# Acquisition_module.net
KiCad netlist of a schematic drawn in Altium Designer
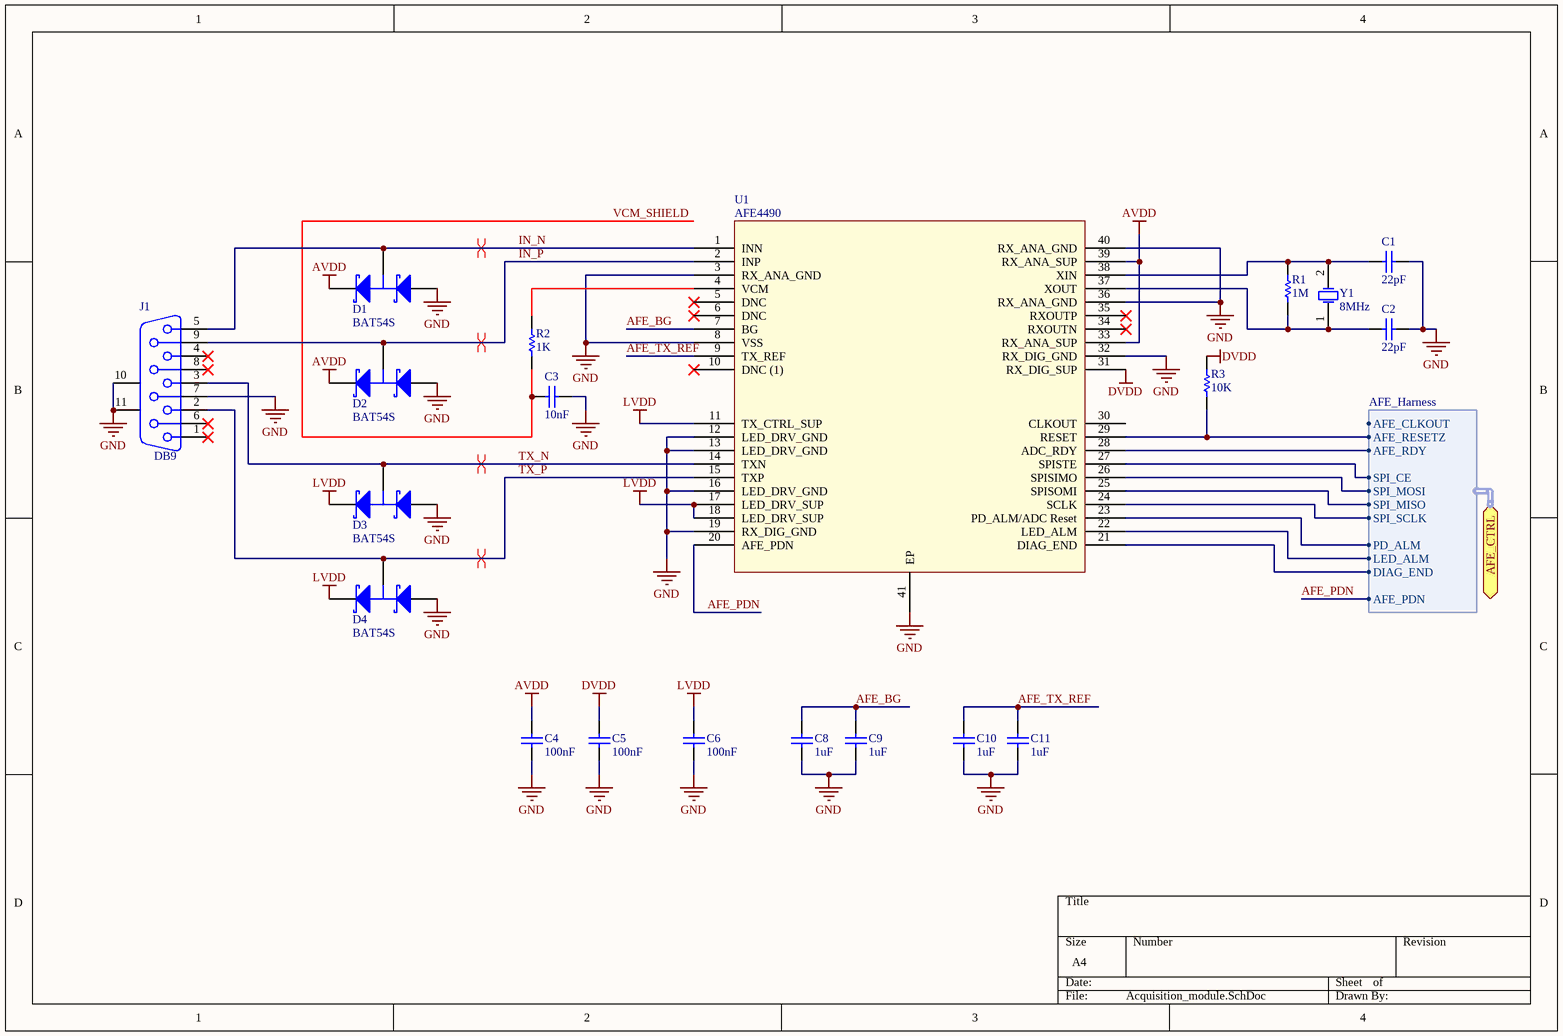
[diagram p0: Acquisition_module.SchDoc]

(export (version "E")
  (design (tool "Eeschema 10.0.6"))
  (components
    (comp (ref "C1")
      (value "22pF")
      (footprint "6-0805_M")
      (description "Capacitor")
      (fields (field (name "Comment") "Cap") (field (name "PUBLISHER") "Altium Limited"))
      (libsource (lib "Miscellaneous Devices") (part "Cap"))
    )
    (comp (ref "C2")
      (value "22pF")
      (footprint "6-0805_M")
      (description "Capacitor")
      (fields (field (name "Comment") "Cap") (field (name "PUBLISHER") "Altium Limited"))
      (libsource (lib "Miscellaneous Devices") (part "Cap"))
    )
    (comp (ref "C3")
      (value "10nF")
      (footprint "6-0805_M")
      (description "Capacitor")
      (fields (field (name "Comment") "Cap") (field (name "PUBLISHER") "Altium Limited"))
      (libsource (lib "Miscellaneous Devices") (part "Cap"))
    )
    (comp (ref "C4")
      (value "100nF")
      (footprint "6-0805_M")
      (description "Capacitor")
      (fields (field (name "Comment") "Cap") (field (name "PUBLISHER") "Altium Limited"))
      (libsource (lib "Miscellaneous Devices") (part "Cap"))
    )
    (comp (ref "C5")
      (value "100nF")
      (footprint "6-0805_M")
      (description "Capacitor")
      (fields (field (name "Comment") "Cap") (field (name "PUBLISHER") "Altium Limited"))
      (libsource (lib "Miscellaneous Devices") (part "Cap"))
    )
    (comp (ref "C6")
      (value "100nF")
      (footprint "6-0805_M")
      (description "Capacitor")
      (fields (field (name "Comment") "Cap") (field (name "PUBLISHER") "Altium Limited"))
      (libsource (lib "Miscellaneous Devices") (part "Cap"))
    )
    (comp (ref "C8")
      (value "1uF")
      (footprint "6-0805_M")
      (description "Capacitor")
      (fields (field (name "Comment") "Cap") (field (name "PUBLISHER") "Altium Limited"))
      (libsource (lib "Miscellaneous Devices") (part "Cap"))
    )
    (comp (ref "C9")
      (value "1uF")
      (footprint "6-0805_M")
      (description "Capacitor")
      (fields (field (name "Comment") "Cap") (field (name "PUBLISHER") "Altium Limited"))
      (libsource (lib "Miscellaneous Devices") (part "Cap"))
    )
    (comp (ref "C10")
      (value "1uF")
      (footprint "6-0805_M")
      (description "Capacitor")
      (fields (field (name "Comment") "Cap") (field (name "PUBLISHER") "Altium Limited"))
      (libsource (lib "Miscellaneous Devices") (part "Cap"))
    )
    (comp (ref "C11")
      (value "1uF")
      (footprint "6-0805_M")
      (description "Capacitor")
      (fields (field (name "Comment") "Cap") (field (name "PUBLISHER") "Altium Limited"))
      (libsource (lib "Miscellaneous Devices") (part "Cap"))
    )
    (comp (ref "D1")
      (value "BAT54S")
      (footprint "SOT23_N")
      (description "Schottky Barrier Double Diode")
      (fields (field (name "PUBLISHER") "Altium Limited"))
      (libsource (lib "Philips Discrete Diode - Schottky") (part "BAT54S"))
    )
    (comp (ref "D2")
      (value "BAT54S")
      (footprint "SOT23_N")
      (description "Schottky Barrier Double Diode")
      (fields (field (name "PUBLISHER") "Altium Limited"))
      (libsource (lib "Philips Discrete Diode - Schottky") (part "BAT54S"))
    )
    (comp (ref "D3")
      (value "BAT54S")
      (footprint "SOT23_N")
      (description "Schottky Barrier Double Diode")
      (fields (field (name "PUBLISHER") "Altium Limited"))
      (libsource (lib "Philips Discrete Diode - Schottky") (part "BAT54S"))
    )
    (comp (ref "D4")
      (value "BAT54S")
      (footprint "SOT23_N")
      (description "Schottky Barrier Double Diode")
      (fields (field (name "PUBLISHER") "Altium Limited"))
      (libsource (lib "Philips Discrete Diode - Schottky") (part "BAT54S"))
    )
    (comp (ref "J1")
      (value "DB9")
      (footprint "DB9")
      (description "Receptacle Assembly, 9 Position, Right Angle")
      (fields (field (name "PUBLISHER") "Altium Limited"))
      (libsource (lib "Miscellaneous Connectors") (part "D Connector 9"))
    )
    (comp (ref "R1")
      (value "1M")
      (footprint "6-0805_M")
      (description "Resistor")
      (fields (field (name "Comment") "Res1") (field (name "PUBLISHER") "Altium Limited"))
      (libsource (lib "Miscellaneous Devices") (part "Res1"))
    )
    (comp (ref "R2")
      (value "1K")
      (footprint "6-0805_M")
      (description "Resistor")
      (fields (field (name "Comment") "Res1") (field (name "PUBLISHER") "Altium Limited"))
      (libsource (lib "Miscellaneous Devices") (part "Res1"))
    )
    (comp (ref "R3")
      (value "10K")
      (footprint "6-0805_M")
      (description "Resistor")
      (fields (field (name "Comment") "Res1") (field (name "PUBLISHER") "Altium Limited"))
      (libsource (lib "Miscellaneous Devices") (part "Res1"))
    )
    (comp (ref "U1")
      (value "AFE4490")
      (footprint "AFE4490QFN50P680X680X100_HS-41N")
      (description "Integrated Analog Front-End for Pulse Oximeters")
      (libsource (lib "AFE4490") (part "AFE4490"))
    )
    (comp (ref "Y1")
      (value "8MHz")
      (footprint "Crystal SMD")
      (description "Crystal Oscillator")
      (fields (field (name "PUBLISHER") "Altium Limited"))
      (libsource (lib "Miscellaneous Devices") (part "XTAL"))
    )
  )
  (nets
    (net (code "2") (name "/AFE_BG") (class "Default")
      (node (ref "C8") (pin "2") (pinfunction "2_2") (pintype "passive"))
      (node (ref "C9") (pin "2") (pinfunction "2_2") (pintype "passive"))
      (node (ref "U1") (pin "7") (pinfunction "BG_7") (pintype "passive"))
    )
    (net (code "3") (name "/AFE_PDN") (class "Default")
      (node (ref "U1") (pin "20") (pinfunction "AFE_PDN_20") (pintype "passive"))
    )
    (net (code "4") (name "/AFE_RDY") (class "Default")
      (node (ref "U1") (pin "28") (pinfunction "ADC_RDY_28") (pintype "passive"))
    )
    (net (code "5") (name "/AFE_RESETZ") (class "Default")
      (node (ref "R3") (pin "1") (pinfunction "1_1") (pintype "passive"))
      (node (ref "U1") (pin "29") (pinfunction "RESET_29") (pintype "passive"))
    )
    (net (code "6") (name "/AFE_TX_REF") (class "Default")
      (node (ref "C10") (pin "2") (pinfunction "2_2") (pintype "passive"))
      (node (ref "C11") (pin "2") (pinfunction "2_2") (pintype "passive"))
      (node (ref "U1") (pin "9") (pinfunction "TX_REF_9") (pintype "passive"))
    )
    (net (code "7") (name "/DIAG_END") (class "Default")
      (node (ref "U1") (pin "21") (pinfunction "DIAG_END_21") (pintype "passive"))
    )
    (net (code "8") (name "/IN_N") (class "Default")
      (node (ref "D1") (pin "3") (pinfunction "C_3") (pintype "passive"))
      (node (ref "J1") (pin "5") (pinfunction "5_5") (pintype "passive"))
      (node (ref "U1") (pin "1") (pinfunction "INN_1") (pintype "passive"))
    )
    (net (code "9") (name "/IN_P") (class "Default")
      (node (ref "D2") (pin "3") (pinfunction "C_3") (pintype "passive"))
      (node (ref "J1") (pin "9") (pinfunction "9_9") (pintype "passive"))
      (node (ref "U1") (pin "2") (pinfunction "INP_2") (pintype "passive"))
    )
    (net (code "10") (name "/LED_ALM") (class "Default")
      (node (ref "U1") (pin "22") (pinfunction "LED_ALM_22") (pintype "passive"))
    )
    (net (code "11") (name "/PD_ALM") (class "Default")
      (node (ref "U1") (pin "23") (pinfunction "PD_ALM/ADC_Reset_23") (pintype "passive"))
    )
    (net (code "12") (name "/SPI_CE") (class "Default")
      (node (ref "U1") (pin "27") (pinfunction "SPISTE_27") (pintype "passive"))
    )
    (net (code "13") (name "/SPI_MISO") (class "Default")
      (node (ref "U1") (pin "25") (pinfunction "SPISOMI_25") (pintype "passive"))
    )
    (net (code "14") (name "/SPI_MOSI") (class "Default")
      (node (ref "U1") (pin "26") (pinfunction "SPISIMO_26") (pintype "passive"))
    )
    (net (code "15") (name "/SPI_SCLK") (class "Default")
      (node (ref "U1") (pin "24") (pinfunction "SCLK_24") (pintype "passive"))
    )
    (net (code "16") (name "/TX_N") (class "Default")
      (node (ref "D3") (pin "3") (pinfunction "C_3") (pintype "passive"))
      (node (ref "J1") (pin "3") (pinfunction "3_3") (pintype "passive"))
      (node (ref "U1") (pin "14") (pinfunction "TXN_14") (pintype "passive"))
    )
    (net (code "17") (name "/TX_P") (class "Default")
      (node (ref "D4") (pin "3") (pinfunction "C_3") (pintype "passive"))
      (node (ref "J1") (pin "2") (pinfunction "2_2") (pintype "passive"))
      (node (ref "U1") (pin "15") (pinfunction "TXP_15") (pintype "passive"))
    )
    (net (code "18") (name "/VCM_SHIELD") (class "Default")
      (node (ref "C3") (pin "2") (pinfunction "2_2") (pintype "passive"))
      (node (ref "R2") (pin "1") (pinfunction "1_1") (pintype "passive"))
    )
    (net (code "20") (name "AVDD") (class "Default")
      (node (ref "C4") (pin "2") (pinfunction "2_2") (pintype "passive"))
      (node (ref "D1") (pin "2") (pinfunction "K_2") (pintype "passive"))
      (node (ref "D2") (pin "2") (pinfunction "K_2") (pintype "passive"))
      (node (ref "U1") (pin "33") (pinfunction "RX_ANA_SUP_33") (pintype "passive"))
      (node (ref "U1") (pin "39") (pinfunction "RX_ANA_SUP_39") (pintype "passive"))
    )
    (net (code "21") (name "DVDD") (class "Default")
      (node (ref "C5") (pin "2") (pinfunction "2_2") (pintype "passive"))
      (node (ref "R3") (pin "2") (pinfunction "2_2") (pintype "passive"))
      (node (ref "U1") (pin "31") (pinfunction "RX_DIG_SUP_31") (pintype "passive"))
    )
    (net (code "22") (name "GND") (class "Default")
      (node (ref "C1") (pin "1") (pinfunction "1_1") (pintype "passive"))
      (node (ref "C10") (pin "1") (pinfunction "1_1") (pintype "passive"))
      (node (ref "C11") (pin "1") (pinfunction "1_1") (pintype "passive"))
      (node (ref "C2") (pin "1") (pinfunction "1_1") (pintype "passive"))
      (node (ref "C3") (pin "1") (pinfunction "1_1") (pintype "passive"))
      (node (ref "C4") (pin "1") (pinfunction "1_1") (pintype "passive"))
      (node (ref "C5") (pin "1") (pinfunction "1_1") (pintype "passive"))
      (node (ref "C6") (pin "1") (pinfunction "1_1") (pintype "passive"))
      (node (ref "C8") (pin "1") (pinfunction "1_1") (pintype "passive"))
      (node (ref "C9") (pin "1") (pinfunction "1_1") (pintype "passive"))
      (node (ref "D1") (pin "1") (pinfunction "A_1") (pintype "passive"))
      (node (ref "D2") (pin "1") (pinfunction "A_1") (pintype "passive"))
      (node (ref "D3") (pin "1") (pinfunction "A_1") (pintype "passive"))
      (node (ref "D4") (pin "1") (pinfunction "A_1") (pintype "passive"))
      (node (ref "J1") (pin "10") (pinfunction "MH1_10") (pintype "passive"))
      (node (ref "J1") (pin "11") (pinfunction "MH2_11") (pintype "passive"))
      (node (ref "J1") (pin "7") (pinfunction "7_7") (pintype "passive"))
      (node (ref "U1") (pin "12") (pinfunction "LED_DRV_GND_12") (pintype "passive"))
      (node (ref "U1") (pin "13") (pinfunction "LED_DRV_GND_13") (pintype "passive"))
      (node (ref "U1") (pin "16") (pinfunction "LED_DRV_GND_16") (pintype "passive"))
      (node (ref "U1") (pin "19") (pinfunction "RX_DIG_GND_19") (pintype "passive"))
      (node (ref "U1") (pin "3") (pinfunction "RX_ANA_GND_3") (pintype "passive"))
      (node (ref "U1") (pin "32") (pinfunction "RX_DIG_GND_32") (pintype "passive"))
      (node (ref "U1") (pin "36") (pinfunction "RX_ANA_GND_36") (pintype "passive"))
      (node (ref "U1") (pin "40") (pinfunction "RX_ANA_GND_40") (pintype "passive"))
      (node (ref "U1") (pin "41") (pinfunction "EP_41") (pintype "passive"))
      (node (ref "U1") (pin "8") (pinfunction "VSS_8") (pintype "passive"))
    )
    (net (code "23") (name "LVDD") (class "Default")
      (node (ref "C6") (pin "2") (pinfunction "2_2") (pintype "passive"))
      (node (ref "D3") (pin "2") (pinfunction "K_2") (pintype "passive"))
      (node (ref "D4") (pin "2") (pinfunction "K_2") (pintype "passive"))
      (node (ref "U1") (pin "11") (pinfunction "TX_CTRL_SUP_11") (pintype "passive"))
      (node (ref "U1") (pin "17") (pinfunction "LED_DRV_SUP_17") (pintype "passive"))
      (node (ref "U1") (pin "18") (pinfunction "LED_DRV_SUP_18") (pintype "passive"))
    )
    (net (code "24") (name "Net-(U1-VCM)") (class "Default")
      (node (ref "R2") (pin "2") (pinfunction "2_2") (pintype "passive"))
      (node (ref "U1") (pin "4") (pinfunction "VCM_4") (pintype "passive"))
    )
    (net (code "25") (name "Net-(U1-XIN)") (class "Default")
      (node (ref "C1") (pin "2") (pinfunction "2_2") (pintype "passive"))
      (node (ref "R1") (pin "1") (pinfunction "1_1") (pintype "passive"))
      (node (ref "U1") (pin "38") (pinfunction "XIN_38") (pintype "passive"))
      (node (ref "Y1") (pin "2") (pinfunction "OSC2_2") (pintype "passive"))
    )
    (net (code "26") (name "Net-(U1-XOUT)") (class "Default")
      (node (ref "C2") (pin "2") (pinfunction "2_2") (pintype "passive"))
      (node (ref "R1") (pin "2") (pinfunction "2_2") (pintype "passive"))
      (node (ref "U1") (pin "37") (pinfunction "XOUT_37") (pintype "passive"))
      (node (ref "Y1") (pin "1") (pinfunction "OSC1_1") (pintype "passive"))
    )
    (net (code "27") (name "unconnected-(J1-Pad1)") (class "Default")
      (node (ref "J1") (pin "1") (pinfunction "1_1") (pintype "passive+no_connect"))
    )
    (net (code "28") (name "unconnected-(J1-Pad4)") (class "Default")
      (node (ref "J1") (pin "4") (pinfunction "4_4") (pintype "passive+no_connect"))
    )
    (net (code "29") (name "unconnected-(J1-Pad6)") (class "Default")
      (node (ref "J1") (pin "6") (pinfunction "6_6") (pintype "passive+no_connect"))
    )
    (net (code "30") (name "unconnected-(J1-Pad8)") (class "Default")
      (node (ref "J1") (pin "8") (pinfunction "8_8") (pintype "passive+no_connect"))
    )
    (net (code "31") (name "unconnected-(U1-CLKOUT-Pad30)") (class "Default")
      (node (ref "U1") (pin "30") (pinfunction "CLKOUT_30") (pintype "passive"))
    )
    (net (code "32") (name "unconnected-(U1-DNC-Pad5)") (class "Default")
      (node (ref "U1") (pin "5") (pinfunction "DNC_5") (pintype "passive+no_connect"))
    )
    (net (code "33") (name "unconnected-(U1-DNC-Pad6)") (class "Default")
      (node (ref "U1") (pin "6") (pinfunction "DNC_6") (pintype "passive+no_connect"))
    )
    (net (code "34") (name "unconnected-(U1-DNC_(1)-Pad10)") (class "Default")
      (node (ref "U1") (pin "10") (pinfunction "DNC_(1)_10") (pintype "passive+no_connect"))
    )
    (net (code "35") (name "unconnected-(U1-RXOUTN-Pad34)") (class "Default")
      (node (ref "U1") (pin "34") (pinfunction "RXOUTN_34") (pintype "passive+no_connect"))
    )
    (net (code "36") (name "unconnected-(U1-RXOUTP-Pad35)") (class "Default")
      (node (ref "U1") (pin "35") (pinfunction "RXOUTP_35") (pintype "passive+no_connect"))
    )
  )
)
